# Sheet4.net
KiCad netlist of a schematic drawn in Altium Designer
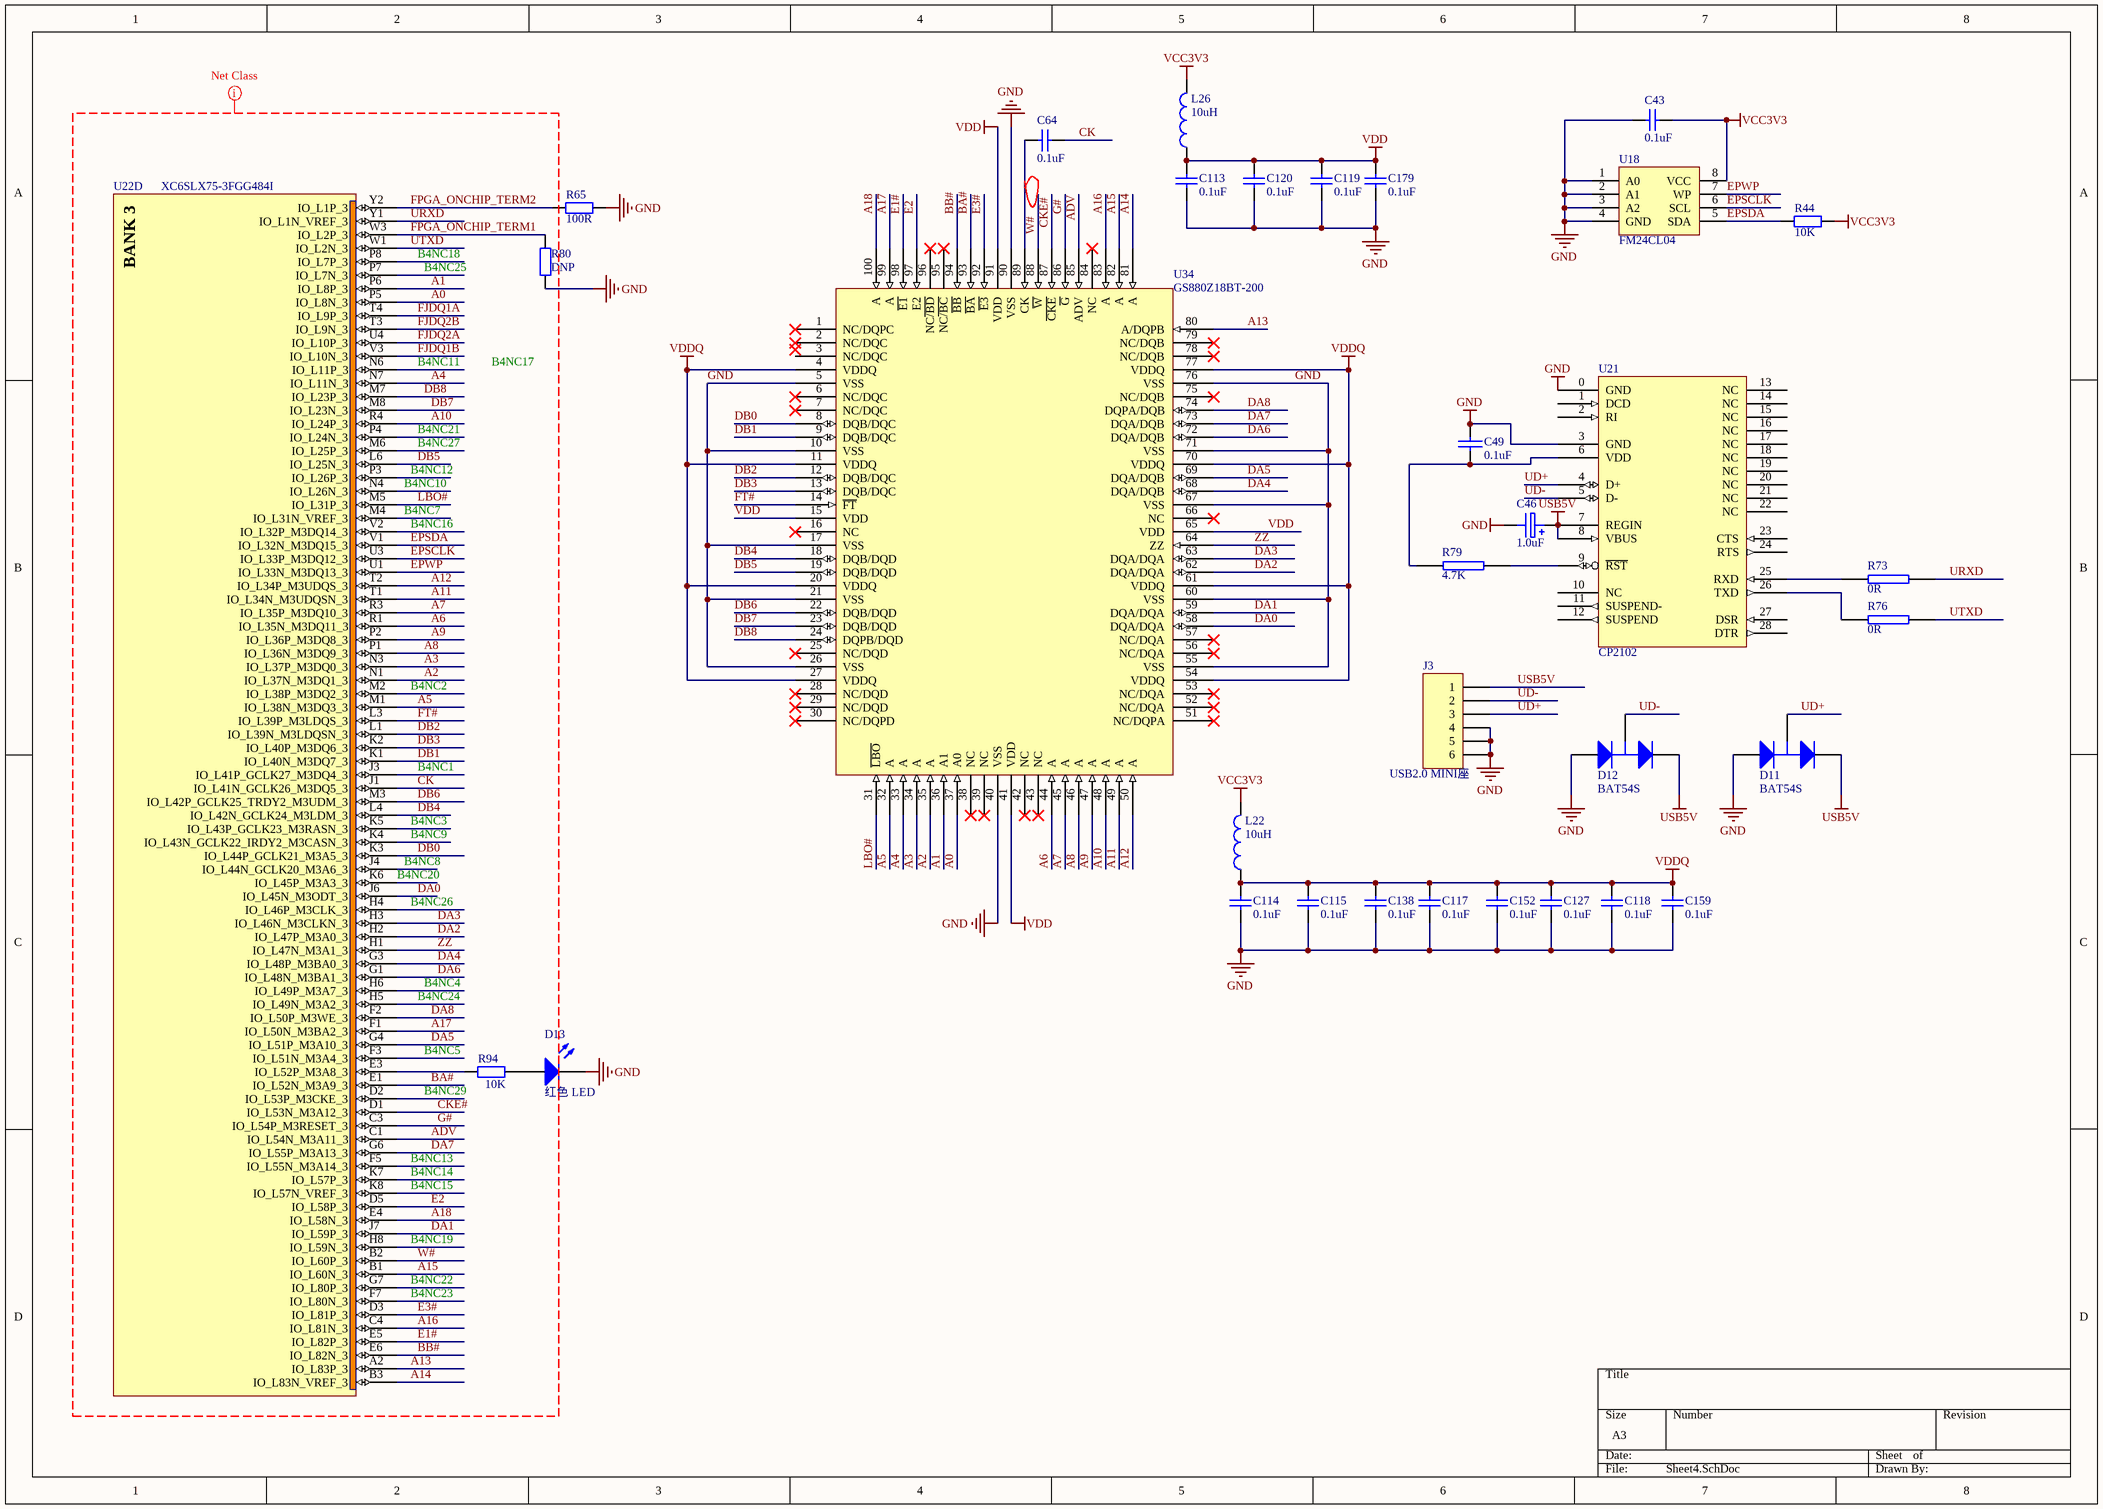
[diagram p0: Sheet4.SchDoc]

(export (version "E")
  (design (tool "Eeschema 10.0.6"))
  (components
    (comp (ref "C43")
      (value "0.1uF")
      (footprint "0603C")
      (description "Capacitor")
      (fields (field (name "PUBLISHER") "Altium Limited"))
      (libsource (lib "Miscellaneous Devices") (part "Cap"))
    )
    (comp (ref "C46") (value "1.0uF") (footprint "0805C") (libsource (lib "*") (part "ELECTRO1")))
    (comp (ref "C49")
      (value "0.1uF")
      (footprint "0603C")
      (description "Capacitor")
      (libsource (lib "*") (part "CAP"))
    )
    (comp (ref "C64")
      (value "0.1uF")
      (footprint "0402C")
      (description "Capacitor")
      (fields (field (name "PUBLISHER") "Altium Limited"))
      (libsource (lib "Miscellaneous Devices") (part "Cap"))
    )
    (comp (ref "C113")
      (value "0.1uF")
      (footprint "0402C")
      (description "Capacitor")
      (fields (field (name "PUBLISHER") "Altium Limited"))
      (libsource (lib "Miscellaneous Devices") (part "Cap"))
    )
    (comp (ref "C114")
      (value "0.1uF")
      (footprint "0402C")
      (description "Capacitor")
      (fields (field (name "PUBLISHER") "Altium Limited"))
      (libsource (lib "Miscellaneous Devices") (part "Cap"))
    )
    (comp (ref "C115")
      (value "0.1uF")
      (footprint "0402C")
      (description "Capacitor")
      (fields (field (name "PUBLISHER") "Altium Limited"))
      (libsource (lib "Miscellaneous Devices") (part "Cap"))
    )
    (comp (ref "C117")
      (value "0.1uF")
      (footprint "0402C")
      (description "Capacitor")
      (fields (field (name "PUBLISHER") "Altium Limited"))
      (libsource (lib "Miscellaneous Devices") (part "Cap"))
    )
    (comp (ref "C118")
      (value "0.1uF")
      (footprint "0402C")
      (description "Capacitor")
      (fields (field (name "PUBLISHER") "Altium Limited"))
      (libsource (lib "Miscellaneous Devices") (part "Cap"))
    )
    (comp (ref "C119")
      (value "0.1uF")
      (footprint "0402C")
      (description "Capacitor")
      (fields (field (name "PUBLISHER") "Altium Limited"))
      (libsource (lib "Miscellaneous Devices") (part "Cap"))
    )
    (comp (ref "C120")
      (value "0.1uF")
      (footprint "0402C")
      (description "Capacitor")
      (fields (field (name "PUBLISHER") "Altium Limited"))
      (libsource (lib "Miscellaneous Devices") (part "Cap"))
    )
    (comp (ref "C127")
      (value "0.1uF")
      (footprint "0402C")
      (description "Capacitor")
      (fields (field (name "PUBLISHER") "Altium Limited"))
      (libsource (lib "Miscellaneous Devices") (part "Cap"))
    )
    (comp (ref "C138")
      (value "0.1uF")
      (footprint "0402C")
      (description "Capacitor")
      (fields (field (name "PUBLISHER") "Altium Limited"))
      (libsource (lib "Miscellaneous Devices") (part "Cap"))
    )
    (comp (ref "C152")
      (value "0.1uF")
      (footprint "0402C")
      (description "Capacitor")
      (fields (field (name "PUBLISHER") "Altium Limited"))
      (libsource (lib "Miscellaneous Devices") (part "Cap"))
    )
    (comp (ref "C159")
      (value "0.1uF")
      (footprint "0402C")
      (description "Capacitor")
      (fields (field (name "PUBLISHER") "Altium Limited"))
      (libsource (lib "Miscellaneous Devices") (part "Cap"))
    )
    (comp (ref "C179")
      (value "0.1uF")
      (footprint "0402C")
      (description "Capacitor")
      (fields (field (name "PUBLISHER") "Altium Limited"))
      (libsource (lib "Miscellaneous Devices") (part "Cap"))
    )
    (comp (ref "D11")
      (value "BAT54S")
      (footprint "SOT23-3L")
      (description "Silicon Switching Diode Array for High-Speed Switching")
      (fields (field (name "PUBLISHER") "Altium Limited"))
      (libsource (lib "Infineon Discrete Diode") (part "BAV99"))
    )
    (comp (ref "D12")
      (value "BAT54S")
      (footprint "SOT23-3L")
      (description "Silicon Switching Diode Array for High-Speed Switching")
      (fields (field (name "PUBLISHER") "Altium Limited"))
      (libsource (lib "Infineon Discrete Diode") (part "BAV99"))
    )
    (comp (ref "D13")
      (value "红色 LED")
      (footprint "0805LED")
      (description "Typical INFRARED GaAs LED")
      (fields (field (name "PUBLISHER") "Altium Limited"))
      (libsource (lib "Miscellaneous Devices") (part "LED0"))
    )
    (comp (ref "J3")
      (value "USB2.0 MINI座")
      (footprint "HDR1X4")
      (description "Header, 6-Pin")
      (fields (field (name "PUBLISHER") "Altium Limited"))
      (libsource (lib "Miscellaneous Connectors") (part "Header 6"))
    )
    (comp (ref "L22")
      (value "10uH")
      (footprint "1206L")
      (description "Inductor")
      (fields (field (name "PUBLISHER") "Altium Limited"))
      (libsource (lib "Miscellaneous Devices") (part "Inductor"))
    )
    (comp (ref "L26")
      (value "10uH")
      (footprint "1206L")
      (description "Inductor")
      (fields (field (name "PUBLISHER") "Altium Limited"))
      (libsource (lib "Miscellaneous Devices") (part "Inductor"))
    )
    (comp (ref "R44") (value "10K") (footprint "0603R") (libsource (lib "Custom Schlib") (part "Resistor")))
    (comp (ref "R65")
      (value "100R")
      (footprint "0603R")
      (description "Resistor")
      (fields (field (name "PUBLISHER") "Altium Limited"))
      (libsource (lib "Miscellaneous Devices") (part "Res2"))
    )
    (comp (ref "R73") (value "0R") (footprint "0603R") (libsource (lib "*") (part "RES2")))
    (comp (ref "R76") (value "0R") (footprint "0603R") (libsource (lib "*") (part "RES2")))
    (comp (ref "R79") (value "4.7K") (footprint "0603R") (libsource (lib "*") (part "RES2")))
    (comp (ref "R80")
      (value "DNP")
      (footprint "0603R")
      (description "Resistor")
      (fields (field (name "PUBLISHER") "Altium Limited"))
      (libsource (lib "") (part "Res2_1"))
    )
    (comp (ref "R94")
      (value "10K")
      (footprint "0603R")
      (description "Resistor")
      (fields (field (name "PUBLISHER") "Altium Limited"))
      (libsource (lib "Miscellaneous Devices") (part "Res2"))
    )
    (comp (ref "U18")
      (value "FM24CL04")
      (footprint "so_8")
      (libsource (lib "Custom Schlib") (part "FM24CL04"))
    )
    (comp (ref "U21")
      (value "CP2102")
      (footprint "MLP-28")
      (description "433MHZ PSK/FM/AM/Data Transceiver")
      (libsource (lib "*") (part "RF2906(28)"))
    )
    (comp (ref "U22")
      (value "XC6SLX75-3FGG484I")
      (footprint "FGG484")
      (fields (field (name "PUBLISHER") "Altium Limited"))
      (libsource (lib "Xilinx Spartan-6") (part "XC6SLX45-L1FGG484I"))
    )
    (comp (ref "U34")
      (value "GS880Z18BT-200")
      (footprint "QFP65P1680X2280-100N")
      (libsource (lib "Mpd_Fpga_2") (part "GS880Z18BT100"))
    )
  )
  (nets
    (net (code "1") (name "/A0") (class "Default")
      (node (ref "U22") (pin "P5") (pinfunction "IO_L8N_3_P5") (pintype "bidirectional"))
      (node (ref "U34") (pin "37") (pinfunction "A0_37") (pintype "input"))
    )
    (net (code "2") (name "/A1") (class "Default")
      (node (ref "U22") (pin "P6") (pinfunction "IO_L8P_3_P6") (pintype "bidirectional"))
      (node (ref "U34") (pin "36") (pinfunction "A1_36") (pintype "input"))
    )
    (net (code "3") (name "/A2") (class "Default")
      (node (ref "U22") (pin "N1") (pinfunction "IO_L37N_M3DQ1_3_N1") (pintype "bidirectional"))
      (node (ref "U34") (pin "35") (pinfunction "A_35") (pintype "input"))
    )
    (net (code "4") (name "/A3") (class "Default")
      (node (ref "U22") (pin "N3") (pinfunction "IO_L37P_M3DQ0_3_N3") (pintype "bidirectional"))
      (node (ref "U34") (pin "34") (pinfunction "A_34") (pintype "input"))
    )
    (net (code "5") (name "/A4") (class "Default")
      (node (ref "U22") (pin "N7") (pinfunction "IO_L11N_3_N7") (pintype "bidirectional"))
      (node (ref "U34") (pin "33") (pinfunction "A_33") (pintype "input"))
    )
    (net (code "6") (name "/A5") (class "Default")
      (node (ref "U22") (pin "M1") (pinfunction "IO_L38N_M3DQ3_3_M1") (pintype "bidirectional"))
      (node (ref "U34") (pin "32") (pinfunction "A_32") (pintype "input"))
    )
    (net (code "7") (name "/A6") (class "Default")
      (node (ref "U22") (pin "R1") (pinfunction "IO_L35N_M3DQ11_3_R1") (pintype "bidirectional"))
      (node (ref "U34") (pin "44") (pinfunction "A_44") (pintype "input"))
    )
    (net (code "8") (name "/A7") (class "Default")
      (node (ref "U22") (pin "R3") (pinfunction "IO_L35P_M3DQ10_3_R3") (pintype "bidirectional"))
      (node (ref "U34") (pin "45") (pinfunction "A_45") (pintype "input"))
    )
    (net (code "9") (name "/A8") (class "Default")
      (node (ref "U22") (pin "P1") (pinfunction "IO_L36N_M3DQ9_3_P1") (pintype "bidirectional"))
      (node (ref "U34") (pin "46") (pinfunction "A_46") (pintype "input"))
    )
    (net (code "10") (name "/A9") (class "Default")
      (node (ref "U22") (pin "P2") (pinfunction "IO_L36P_M3DQ8_3_P2") (pintype "bidirectional"))
      (node (ref "U34") (pin "47") (pinfunction "A_47") (pintype "input"))
    )
    (net (code "11") (name "/A10") (class "Default")
      (node (ref "U22") (pin "R4") (pinfunction "IO_L24P_3_R4") (pintype "bidirectional"))
      (node (ref "U34") (pin "48") (pinfunction "A_48") (pintype "input"))
    )
    (net (code "12") (name "/A11") (class "Default")
      (node (ref "U22") (pin "T1") (pinfunction "IO_L34N_M3UDQSN_3_T1") (pintype "bidirectional"))
      (node (ref "U34") (pin "49") (pinfunction "A_49") (pintype "input"))
    )
    (net (code "13") (name "/A12") (class "Default")
      (node (ref "U22") (pin "T2") (pinfunction "IO_L34P_M3UDQS_3_T2") (pintype "bidirectional"))
      (node (ref "U34") (pin "50") (pinfunction "A_50") (pintype "input"))
    )
    (net (code "14") (name "/A13") (class "Default")
      (node (ref "U22") (pin "A2") (pinfunction "IO_L83P_3_A2") (pintype "bidirectional"))
      (node (ref "U34") (pin "80") (pinfunction "A/DQPB_80") (pintype "input"))
    )
    (net (code "15") (name "/A14") (class "Default")
      (node (ref "U22") (pin "B3") (pinfunction "IO_L83N_VREF_3_B3") (pintype "bidirectional"))
      (node (ref "U34") (pin "81") (pinfunction "A_81") (pintype "input"))
    )
    (net (code "16") (name "/A15") (class "Default")
      (node (ref "U22") (pin "B1") (pinfunction "IO_L60N_3_B1") (pintype "bidirectional"))
      (node (ref "U34") (pin "82") (pinfunction "A_82") (pintype "input"))
    )
    (net (code "17") (name "/A16") (class "Default")
      (node (ref "U22") (pin "C4") (pinfunction "IO_L81N_3_C4") (pintype "bidirectional"))
      (node (ref "U34") (pin "83") (pinfunction "A_83") (pintype "input"))
    )
    (net (code "18") (name "/A17") (class "Default")
      (node (ref "U22") (pin "F1") (pinfunction "IO_L50N_M3BA2_3_F1") (pintype "bidirectional"))
      (node (ref "U34") (pin "99") (pinfunction "A_99") (pintype "input"))
    )
    (net (code "19") (name "/A18") (class "Default")
      (node (ref "U22") (pin "E4") (pinfunction "IO_L58N_3_E4") (pintype "bidirectional"))
      (node (ref "U34") (pin "100") (pinfunction "A_100") (pintype "input"))
    )
    (net (code "20") (name "/ADV") (class "Default")
      (node (ref "U22") (pin "C1") (pinfunction "IO_L54N_M3A11_3_C1") (pintype "bidirectional"))
      (node (ref "U34") (pin "85") (pinfunction "ADV_85") (pintype "input"))
    )
    (net (code "21") (name "/B4NC1") (class "Default")
      (node (ref "U22") (pin "J3") (pinfunction "IO_L41P_GCLK27_M3DQ4_3_J3") (pintype "bidirectional"))
    )
    (net (code "22") (name "/B4NC2") (class "Default")
      (node (ref "U22") (pin "M2") (pinfunction "IO_L38P_M3DQ2_3_M2") (pintype "bidirectional"))
    )
    (net (code "23") (name "/B4NC3") (class "Default")
      (node (ref "U22") (pin "K5") (pinfunction "IO_L43P_GCLK23_M3RASN_3_K5") (pintype "bidirectional"))
    )
    (net (code "24") (name "/B4NC4") (class "Default")
      (node (ref "U22") (pin "H6") (pinfunction "IO_L49P_M3A7_3_H6") (pintype "bidirectional"))
    )
    (net (code "25") (name "/B4NC5") (class "Default")
      (node (ref "U22") (pin "F3") (pinfunction "IO_L51N_M3A4_3_F3") (pintype "bidirectional"))
    )
    (net (code "26") (name "/B4NC7") (class "Default")
      (node (ref "U22") (pin "M4") (pinfunction "IO_L31N_VREF_3_M4") (pintype "bidirectional"))
    )
    (net (code "27") (name "/B4NC8") (class "Default")
      (node (ref "U22") (pin "J4") (pinfunction "IO_L44N_GCLK20_M3A6_3_J4") (pintype "bidirectional"))
    )
    (net (code "28") (name "/B4NC9") (class "Default")
      (node (ref "U22") (pin "K4") (pinfunction "IO_L43N_GCLK22_IRDY2_M3CASN_3_K4") (pintype "bidirectional"))
    )
    (net (code "29") (name "/B4NC10") (class "Default")
      (node (ref "U22") (pin "N4") (pinfunction "IO_L26N_3_N4") (pintype "bidirectional"))
    )
    (net (code "30") (name "/B4NC11") (class "Default")
      (node (ref "U22") (pin "N6") (pinfunction "IO_L11P_3_N6") (pintype "bidirectional"))
    )
    (net (code "31") (name "/B4NC12") (class "Default")
      (node (ref "U22") (pin "P3") (pinfunction "IO_L26P_3_P3") (pintype "bidirectional"))
    )
    (net (code "32") (name "/B4NC13") (class "Default")
      (node (ref "U22") (pin "F5") (pinfunction "IO_L55N_M3A14_3_F5") (pintype "bidirectional"))
    )
    (net (code "33") (name "/B4NC14") (class "Default")
      (node (ref "U22") (pin "K7") (pinfunction "IO_L57P_3_K7") (pintype "bidirectional"))
    )
    (net (code "34") (name "/B4NC15") (class "Default")
      (node (ref "U22") (pin "K8") (pinfunction "IO_L57N_VREF_3_K8") (pintype "bidirectional"))
    )
    (net (code "35") (name "/B4NC16") (class "Default")
      (node (ref "U22") (pin "V2") (pinfunction "IO_L32P_M3DQ14_3_V2") (pintype "bidirectional"))
    )
    (net (code "37") (name "/B4NC18") (class "Default")
      (node (ref "U22") (pin "P8") (pinfunction "IO_L7P_3_P8") (pintype "bidirectional"))
    )
    (net (code "38") (name "/B4NC19") (class "Default")
      (node (ref "U22") (pin "H8") (pinfunction "IO_L59N_3_H8") (pintype "bidirectional"))
    )
    (net (code "39") (name "/B4NC20") (class "Default")
      (node (ref "U22") (pin "K6") (pinfunction "IO_L45P_M3A3_3_K6") (pintype "bidirectional"))
    )
    (net (code "40") (name "/B4NC21") (class "Default")
      (node (ref "U22") (pin "P4") (pinfunction "IO_L24N_3_P4") (pintype "bidirectional"))
    )
    (net (code "41") (name "/B4NC22") (class "Default")
      (node (ref "U22") (pin "G7") (pinfunction "IO_L80P_3_G7") (pintype "bidirectional"))
    )
    (net (code "42") (name "/B4NC23") (class "Default")
      (node (ref "U22") (pin "F7") (pinfunction "IO_L80N_3_F7") (pintype "bidirectional"))
    )
    (net (code "43") (name "/B4NC24") (class "Default")
      (node (ref "U22") (pin "H5") (pinfunction "IO_L49N_M3A2_3_H5") (pintype "bidirectional"))
    )
    (net (code "44") (name "/B4NC25") (class "Default")
      (node (ref "U22") (pin "P7") (pinfunction "IO_L7N_3_P7") (pintype "bidirectional"))
    )
    (net (code "45") (name "/B4NC26") (class "Default")
      (node (ref "U22") (pin "H4") (pinfunction "IO_L46P_M3CLK_3_H4") (pintype "bidirectional"))
    )
    (net (code "46") (name "/B4NC27") (class "Default")
      (node (ref "U22") (pin "M6") (pinfunction "IO_L25P_3_M6") (pintype "bidirectional"))
    )
    (net (code "47") (name "/B4NC29") (class "Default")
      (node (ref "U22") (pin "D2") (pinfunction "IO_L53P_M3CKE_3_D2") (pintype "bidirectional"))
    )
    (net (code "48") (name "/BA#") (class "Default")
      (node (ref "U22") (pin "E1") (pinfunction "IO_L52N_M3A9_3_E1") (pintype "bidirectional"))
      (node (ref "U34") (pin "93") (pinfunction "~{BA}_93") (pintype "input"))
    )
    (net (code "49") (name "/BB#") (class "Default")
      (node (ref "U22") (pin "E6") (pinfunction "IO_L82N_3_E6") (pintype "bidirectional"))
      (node (ref "U34") (pin "94") (pinfunction "~{BB}_94") (pintype "input"))
    )
    (net (code "50") (name "/CK") (class "Default")
      (node (ref "C64") (pin "1") (pinfunction "1_1") (pintype "passive"))
      (node (ref "U22") (pin "J1") (pinfunction "IO_L41N_GCLK26_M3DQ5_3_J1") (pintype "bidirectional"))
    )
    (net (code "51") (name "/CKE#") (class "Default")
      (node (ref "U22") (pin "D1") (pinfunction "IO_L53N_M3A12_3_D1") (pintype "bidirectional"))
      (node (ref "U34") (pin "87") (pinfunction "~{CKE}_87") (pintype "input"))
    )
    (net (code "52") (name "/DA0") (class "Default")
      (node (ref "U22") (pin "J6") (pinfunction "IO_L45N_M3ODT_3_J6") (pintype "bidirectional"))
      (node (ref "U34") (pin "58") (pinfunction "DQA/DQA_58") (pintype "bidirectional"))
    )
    (net (code "53") (name "/DA1") (class "Default")
      (node (ref "U22") (pin "J7") (pinfunction "IO_L59P_3_J7") (pintype "bidirectional"))
      (node (ref "U34") (pin "59") (pinfunction "DQA/DQA_59") (pintype "bidirectional"))
    )
    (net (code "54") (name "/DA2") (class "Default")
      (node (ref "U22") (pin "H2") (pinfunction "IO_L47P_M3A0_3_H2") (pintype "bidirectional"))
      (node (ref "U34") (pin "62") (pinfunction "DQA/DQA_62") (pintype "bidirectional"))
    )
    (net (code "55") (name "/DA3") (class "Default")
      (node (ref "U22") (pin "H3") (pinfunction "IO_L46N_M3CLKN_3_H3") (pintype "bidirectional"))
      (node (ref "U34") (pin "63") (pinfunction "DQA/DQA_63") (pintype "bidirectional"))
    )
    (net (code "56") (name "/DA4") (class "Default")
      (node (ref "U22") (pin "G3") (pinfunction "IO_L48P_M3BA0_3_G3") (pintype "bidirectional"))
      (node (ref "U34") (pin "68") (pinfunction "DQA/DQB_68") (pintype "bidirectional"))
    )
    (net (code "57") (name "/DA5") (class "Default")
      (node (ref "U22") (pin "G4") (pinfunction "IO_L51P_M3A10_3_G4") (pintype "bidirectional"))
      (node (ref "U34") (pin "69") (pinfunction "DQA/DQB_69") (pintype "bidirectional"))
    )
    (net (code "58") (name "/DA6") (class "Default")
      (node (ref "U22") (pin "G1") (pinfunction "IO_L48N_M3BA1_3_G1") (pintype "bidirectional"))
      (node (ref "U34") (pin "72") (pinfunction "DQA/DQB_72") (pintype "bidirectional"))
    )
    (net (code "59") (name "/DA7") (class "Default")
      (node (ref "U22") (pin "G6") (pinfunction "IO_L55P_M3A13_3_G6") (pintype "bidirectional"))
      (node (ref "U34") (pin "73") (pinfunction "DQA/DQB_73") (pintype "bidirectional"))
    )
    (net (code "60") (name "/DA8") (class "Default")
      (node (ref "U22") (pin "F2") (pinfunction "IO_L50P_M3WE_3_F2") (pintype "bidirectional"))
      (node (ref "U34") (pin "74") (pinfunction "DQPA/DQB_74") (pintype "bidirectional"))
    )
    (net (code "61") (name "/DB0") (class "Default")
      (node (ref "U22") (pin "K3") (pinfunction "IO_L44P_GCLK21_M3A5_3_K3") (pintype "bidirectional"))
      (node (ref "U34") (pin "8") (pinfunction "DQB/DQC_8") (pintype "bidirectional"))
    )
    (net (code "62") (name "/DB1") (class "Default")
      (node (ref "U22") (pin "K1") (pinfunction "IO_L40N_M3DQ7_3_K1") (pintype "bidirectional"))
      (node (ref "U34") (pin "9") (pinfunction "DQB/DQC_9") (pintype "bidirectional"))
    )
    (net (code "63") (name "/DB2") (class "Default")
      (node (ref "U22") (pin "L1") (pinfunction "IO_L39N_M3LDQSN_3_L1") (pintype "bidirectional"))
      (node (ref "U34") (pin "12") (pinfunction "DQB/DQC_12") (pintype "bidirectional"))
    )
    (net (code "64") (name "/DB3") (class "Default")
      (node (ref "U22") (pin "K2") (pinfunction "IO_L40P_M3DQ6_3_K2") (pintype "bidirectional"))
      (node (ref "U34") (pin "13") (pinfunction "DQB/DQC_13") (pintype "bidirectional"))
    )
    (net (code "65") (name "/DB4") (class "Default")
      (node (ref "U22") (pin "L4") (pinfunction "IO_L42N_GCLK24_M3LDM_3_L4") (pintype "bidirectional"))
      (node (ref "U34") (pin "18") (pinfunction "DQB/DQD_18") (pintype "bidirectional"))
    )
    (net (code "66") (name "/DB5") (class "Default")
      (node (ref "U22") (pin "L6") (pinfunction "IO_L25N_3_L6") (pintype "bidirectional"))
      (node (ref "U34") (pin "19") (pinfunction "DQB/DQD_19") (pintype "bidirectional"))
    )
    (net (code "67") (name "/DB6") (class "Default")
      (node (ref "U22") (pin "M3") (pinfunction "IO_L42P_GCLK25_TRDY2_M3UDM_3_M3") (pintype "bidirectional"))
      (node (ref "U34") (pin "22") (pinfunction "DQB/DQD_22") (pintype "bidirectional"))
    )
    (net (code "68") (name "/DB7") (class "Default")
      (node (ref "U22") (pin "M8") (pinfunction "IO_L23N_3_M8") (pintype "bidirectional"))
      (node (ref "U34") (pin "23") (pinfunction "DQB/DQD_23") (pintype "bidirectional"))
    )
    (net (code "69") (name "/DB8") (class "Default")
      (node (ref "U22") (pin "M7") (pinfunction "IO_L23P_3_M7") (pintype "bidirectional"))
      (node (ref "U34") (pin "24") (pinfunction "DQPB/DQD_24") (pintype "bidirectional"))
    )
    (net (code "70") (name "/E1#") (class "Default")
      (node (ref "U22") (pin "E5") (pinfunction "IO_L82P_3_E5") (pintype "bidirectional"))
      (node (ref "U34") (pin "98") (pinfunction "~{E1}_98") (pintype "input"))
    )
    (net (code "71") (name "/E2") (class "Default")
      (node (ref "U22") (pin "D5") (pinfunction "IO_L58P_3_D5") (pintype "bidirectional"))
      (node (ref "U34") (pin "97") (pinfunction "E2_97") (pintype "input"))
    )
    (net (code "72") (name "/E3#") (class "Default")
      (node (ref "U22") (pin "D3") (pinfunction "IO_L81P_3_D3") (pintype "bidirectional"))
      (node (ref "U34") (pin "92") (pinfunction "~{E3}_92") (pintype "input"))
    )
    (net (code "73") (name "/EPSCLK") (class "Default")
      (node (ref "U18") (pin "6") (pinfunction "SCL_6") (pintype "passive"))
      (node (ref "U22") (pin "U3") (pinfunction "IO_L33P_M3DQ12_3_U3") (pintype "bidirectional"))
    )
    (net (code "74") (name "/EPSDA") (class "Default")
      (node (ref "R44") (pin "1") (pinfunction "1_1") (pintype "passive"))
      (node (ref "U18") (pin "5") (pinfunction "SDA_5") (pintype "passive"))
      (node (ref "U22") (pin "V1") (pinfunction "IO_L32N_M3DQ15_3_V1") (pintype "bidirectional"))
    )
    (net (code "75") (name "/EPWP") (class "Default")
      (node (ref "U18") (pin "7") (pinfunction "WP_7") (pintype "passive"))
      (node (ref "U22") (pin "U1") (pinfunction "IO_L33N_M3DQ13_3_U1") (pintype "bidirectional"))
    )
    (net (code "76") (name "/FJDQ1A") (class "Default")
      (node (ref "U22") (pin "T4") (pinfunction "IO_L9P_3_T4") (pintype "bidirectional"))
    )
    (net (code "77") (name "/FJDQ1B") (class "Default")
      (node (ref "U22") (pin "V3") (pinfunction "IO_L10N_3_V3") (pintype "bidirectional"))
    )
    (net (code "78") (name "/FJDQ2A") (class "Default")
      (node (ref "U22") (pin "U4") (pinfunction "IO_L10P_3_U4") (pintype "bidirectional"))
    )
    (net (code "79") (name "/FJDQ2B") (class "Default")
      (node (ref "U22") (pin "T3") (pinfunction "IO_L9N_3_T3") (pintype "bidirectional"))
    )
    (net (code "80") (name "/FPGA_ONCHIP_TERM1") (class "Default")
      (node (ref "R80") (pin "1") (pinfunction "1_1") (pintype "passive"))
      (node (ref "U22") (pin "W3") (pinfunction "IO_L2P_3_W3") (pintype "bidirectional"))
    )
    (net (code "81") (name "/FPGA_ONCHIP_TERM2") (class "Default")
      (node (ref "R65") (pin "1") (pinfunction "1_1") (pintype "passive"))
      (node (ref "U22") (pin "Y2") (pinfunction "IO_L1P_3_Y2") (pintype "bidirectional"))
    )
    (net (code "82") (name "/FT#") (class "Default")
      (node (ref "U22") (pin "L3") (pinfunction "IO_L39P_M3LDQS_3_L3") (pintype "bidirectional"))
      (node (ref "U34") (pin "14") (pinfunction "~{FT}_14") (pintype "input"))
    )
    (net (code "83") (name "/G#") (class "Default")
      (node (ref "U22") (pin "C3") (pinfunction "IO_L54P_M3RESET_3_C3") (pintype "bidirectional"))
      (node (ref "U34") (pin "86") (pinfunction "~{G}_86") (pintype "input"))
    )
    (net (code "84") (name "/LBO#") (class "Default")
      (node (ref "U22") (pin "M5") (pinfunction "IO_L31P_3_M5") (pintype "bidirectional"))
      (node (ref "U34") (pin "31") (pinfunction "~{LBO}_31") (pintype "input"))
    )
    (net (code "85") (name "/UD+") (class "Default")
      (node (ref "D11") (pin "3") (pinfunction "C_3") (pintype "passive"))
      (node (ref "J3") (pin "3") (pinfunction "3_3") (pintype "passive"))
      (node (ref "U21") (pin "4") (pinfunction "D+_4") (pintype "bidirectional"))
    )
    (net (code "86") (name "/UD-") (class "Default")
      (node (ref "D12") (pin "3") (pinfunction "C_3") (pintype "passive"))
      (node (ref "J3") (pin "2") (pinfunction "2_2") (pintype "passive"))
      (node (ref "U21") (pin "5") (pinfunction "D-_5") (pintype "bidirectional"))
    )
    (net (code "87") (name "/URXD") (class "Default")
      (node (ref "R73") (pin "1") (pinfunction "1_1") (pintype "passive"))
      (node (ref "U22") (pin "Y1") (pinfunction "IO_L1N_VREF_3_Y1") (pintype "bidirectional"))
    )
    (net (code "88") (name "/UTXD") (class "Default")
      (node (ref "R76") (pin "1") (pinfunction "1_1") (pintype "passive"))
      (node (ref "U22") (pin "W1") (pinfunction "IO_L2N_3_W1") (pintype "bidirectional"))
    )
    (net (code "89") (name "/W#") (class "Default")
      (node (ref "U22") (pin "B2") (pinfunction "IO_L60P_3_B2") (pintype "bidirectional"))
      (node (ref "U34") (pin "88") (pinfunction "~{W}_88") (pintype "input"))
    )
    (net (code "90") (name "/ZZ") (class "Default")
      (node (ref "U22") (pin "H1") (pinfunction "IO_L47N_M3A1_3_H1") (pintype "bidirectional"))
      (node (ref "U34") (pin "64") (pinfunction "ZZ_64") (pintype "input"))
    )
    (net (code "91") (name "GND") (class "Default")
      (node (ref "C113") (pin "1") (pinfunction "1_1") (pintype "passive"))
      (node (ref "C114") (pin "1") (pinfunction "1_1") (pintype "passive"))
      (node (ref "C115") (pin "1") (pinfunction "1_1") (pintype "passive"))
      (node (ref "C117") (pin "1") (pinfunction "1_1") (pintype "passive"))
      (node (ref "C118") (pin "1") (pinfunction "1_1") (pintype "passive"))
      (node (ref "C119") (pin "1") (pinfunction "1_1") (pintype "passive"))
      (node (ref "C120") (pin "1") (pinfunction "1_1") (pintype "passive"))
      (node (ref "C127") (pin "1") (pinfunction "1_1") (pintype "passive"))
      (node (ref "C138") (pin "1") (pinfunction "1_1") (pintype "passive"))
      (node (ref "C152") (pin "1") (pinfunction "1_1") (pintype "passive"))
      (node (ref "C159") (pin "1") (pinfunction "1_1") (pintype "passive"))
      (node (ref "C179") (pin "1") (pinfunction "1_1") (pintype "passive"))
      (node (ref "C43") (pin "2") (pinfunction "2_2") (pintype "passive"))
      (node (ref "C46") (pin "2") (pintype "passive"))
      (node (ref "C49") (pin "2") (pinfunction "2_2") (pintype "passive"))
      (node (ref "D11") (pin "1") (pinfunction "A_1") (pintype "passive"))
      (node (ref "D12") (pin "1") (pinfunction "A_1") (pintype "passive"))
      (node (ref "D13") (pin "2") (pinfunction "K_2") (pintype "passive"))
      (node (ref "J3") (pin "4") (pinfunction "4_4") (pintype "passive"))
      (node (ref "J3") (pin "5") (pinfunction "5_5") (pintype "passive"))
      (node (ref "J3") (pin "6") (pinfunction "6_6") (pintype "passive"))
      (node (ref "R65") (pin "2") (pinfunction "2_2") (pintype "passive"))
      (node (ref "R80") (pin "2") (pinfunction "2_2") (pintype "passive"))
      (node (ref "U18") (pin "1") (pinfunction "A0_1") (pintype "passive"))
      (node (ref "U18") (pin "2") (pinfunction "A1_2") (pintype "passive"))
      (node (ref "U18") (pin "3") (pinfunction "A2_3") (pintype "passive"))
      (node (ref "U18") (pin "4") (pinfunction "GND_4") (pintype "passive"))
      (node (ref "U21") (pin "0") (pinfunction "GND_0") (pintype "power_in"))
      (node (ref "U21") (pin "3") (pinfunction "GND_3") (pintype "power_in"))
      (node (ref "U34") (pin "10") (pinfunction "VSS_10") (pintype "power_in"))
      (node (ref "U34") (pin "17") (pinfunction "VSS_17") (pintype "power_in"))
      (node (ref "U34") (pin "21") (pinfunction "VSS_21") (pintype "power_in"))
      (node (ref "U34") (pin "26") (pinfunction "VSS_26") (pintype "power_in"))
      (node (ref "U34") (pin "40") (pinfunction "VSS_40") (pintype "power_in"))
      (node (ref "U34") (pin "5") (pinfunction "VSS_5") (pintype "power_in"))
      (node (ref "U34") (pin "55") (pinfunction "VSS_55") (pintype "power_in"))
      (node (ref "U34") (pin "60") (pinfunction "VSS_60") (pintype "power_in"))
      (node (ref "U34") (pin "67") (pinfunction "VSS_67") (pintype "power_in"))
      (node (ref "U34") (pin "71") (pinfunction "VSS_71") (pintype "power_in"))
      (node (ref "U34") (pin "76") (pinfunction "VSS_76") (pintype "power_in"))
      (node (ref "U34") (pin "90") (pinfunction "VSS_90") (pintype "power_in"))
    )
    (net (code "92") (name "Net-(D13-A)") (class "Default")
      (node (ref "D13") (pin "1") (pinfunction "A_1") (pintype "passive"))
      (node (ref "R94") (pin "2") (pinfunction "2_2") (pintype "passive"))
    )
    (net (code "93") (name "Net-(U21-RXD)") (class "Default")
      (node (ref "R73") (pin "2") (pinfunction "2_2") (pintype "passive"))
      (node (ref "U21") (pin "25") (pinfunction "RXD_25") (pintype "input"))
    )
    (net (code "94") (name "Net-(U21-TXD)") (class "Default")
      (node (ref "R76") (pin "2") (pinfunction "2_2") (pintype "passive"))
      (node (ref "U21") (pin "26") (pinfunction "TXD_26") (pintype "output"))
    )
    (net (code "95") (name "Net-(U21-VDD)") (class "Default")
      (node (ref "C49") (pin "1") (pinfunction "1_1") (pintype "passive"))
      (node (ref "R79") (pin "2") (pinfunction "2_2") (pintype "passive"))
      (node (ref "U21") (pin "6") (pinfunction "VDD_6") (pintype "power_in"))
    )
    (net (code "96") (name "Net-(U21-~{RST})") (class "Default")
      (node (ref "R79") (pin "1") (pinfunction "1_1") (pintype "passive"))
      (node (ref "U21") (pin "9") (pinfunction "~{RST}_9") (pintype "bidirectional"))
    )
    (net (code "97") (name "Net-(U22D-IO_L52P_M3A8_3)") (class "Default")
      (node (ref "R94") (pin "1") (pinfunction "1_1") (pintype "passive"))
      (node (ref "U22") (pin "E3") (pinfunction "IO_L52P_M3A8_3_E3") (pintype "bidirectional"))
    )
    (net (code "98") (name "Net-(U34-CK)") (class "Default")
      (node (ref "C64") (pin "2") (pinfunction "2_2") (pintype "passive"))
      (node (ref "U34") (pin "89") (pinfunction "CK_89") (pintype "input"))
    )
    (net (code "99") (name "USB5V") (class "Default")
      (node (ref "C46") (pin "1") (pintype "passive"))
      (node (ref "D11") (pin "2") (pinfunction "K_2") (pintype "passive"))
      (node (ref "D12") (pin "2") (pinfunction "K_2") (pintype "passive"))
      (node (ref "J3") (pin "1") (pinfunction "1_1") (pintype "passive"))
      (node (ref "U21") (pin "7") (pinfunction "REGIN_7") (pintype "power_in"))
      (node (ref "U21") (pin "8") (pinfunction "VBUS_8") (pintype "input"))
    )
    (net (code "100") (name "VCC3V3") (class "Default")
      (node (ref "C43") (pin "1") (pinfunction "1_1") (pintype "passive"))
      (node (ref "L22") (pin "2") (pinfunction "2_2") (pintype "passive"))
      (node (ref "L26") (pin "2") (pinfunction "2_2") (pintype "passive"))
      (node (ref "R44") (pin "2") (pinfunction "2_2") (pintype "passive"))
      (node (ref "U18") (pin "8") (pinfunction "VCC_8") (pintype "passive"))
    )
    (net (code "101") (name "VDD") (class "Default")
      (node (ref "C113") (pin "2") (pinfunction "2_2") (pintype "passive"))
      (node (ref "C119") (pin "2") (pinfunction "2_2") (pintype "passive"))
      (node (ref "C120") (pin "2") (pinfunction "2_2") (pintype "passive"))
      (node (ref "C179") (pin "2") (pinfunction "2_2") (pintype "passive"))
      (node (ref "L26") (pin "1") (pinfunction "1_1") (pintype "passive"))
      (node (ref "U34") (pin "15") (pinfunction "VDD_15") (pintype "power_in"))
      (node (ref "U34") (pin "41") (pinfunction "VDD_41") (pintype "power_in"))
      (node (ref "U34") (pin "65") (pinfunction "VDD_65") (pintype "power_in"))
      (node (ref "U34") (pin "91") (pinfunction "VDD_91") (pintype "power_in"))
    )
    (net (code "102") (name "VDDQ") (class "Default")
      (node (ref "C114") (pin "2") (pinfunction "2_2") (pintype "passive"))
      (node (ref "C115") (pin "2") (pinfunction "2_2") (pintype "passive"))
      (node (ref "C117") (pin "2") (pinfunction "2_2") (pintype "passive"))
      (node (ref "C118") (pin "2") (pinfunction "2_2") (pintype "passive"))
      (node (ref "C127") (pin "2") (pinfunction "2_2") (pintype "passive"))
      (node (ref "C138") (pin "2") (pinfunction "2_2") (pintype "passive"))
      (node (ref "C152") (pin "2") (pinfunction "2_2") (pintype "passive"))
      (node (ref "C159") (pin "2") (pinfunction "2_2") (pintype "passive"))
      (node (ref "L22") (pin "1") (pinfunction "1_1") (pintype "passive"))
      (node (ref "U34") (pin "11") (pinfunction "VDDQ_11") (pintype "power_in"))
      (node (ref "U34") (pin "20") (pinfunction "VDDQ_20") (pintype "power_in"))
      (node (ref "U34") (pin "27") (pinfunction "VDDQ_27") (pintype "power_in"))
      (node (ref "U34") (pin "4") (pinfunction "VDDQ_4") (pintype "power_in"))
      (node (ref "U34") (pin "54") (pinfunction "VDDQ_54") (pintype "power_in"))
      (node (ref "U34") (pin "61") (pinfunction "VDDQ_61") (pintype "power_in"))
      (node (ref "U34") (pin "70") (pinfunction "VDDQ_70") (pintype "power_in"))
      (node (ref "U34") (pin "77") (pinfunction "VDDQ_77") (pintype "power_in"))
    )
    (net (code "103") (name "unconnected-(U21-CTS-Pad23)") (class "Default")
      (node (ref "U21") (pin "23") (pinfunction "CTS_23") (pintype "input"))
    )
    (net (code "104") (name "unconnected-(U21-DCD-Pad1)") (class "Default")
      (node (ref "U21") (pin "1") (pinfunction "DCD_1") (pintype "input"))
    )
    (net (code "105") (name "unconnected-(U21-DSR-Pad27)") (class "Default")
      (node (ref "U21") (pin "27") (pinfunction "DSR_27") (pintype "input"))
    )
    (net (code "106") (name "unconnected-(U21-DTR-Pad28)") (class "Default")
      (node (ref "U21") (pin "28") (pinfunction "DTR_28") (pintype "output"))
    )
    (net (code "107") (name "unconnected-(U21-NC-Pad10)") (class "Default")
      (node (ref "U21") (pin "10") (pinfunction "NC_10") (pintype "tri_state"))
    )
    (net (code "108") (name "unconnected-(U21-NC-Pad13)") (class "Default")
      (node (ref "U21") (pin "13") (pinfunction "NC_13") (pintype "tri_state"))
    )
    (net (code "109") (name "unconnected-(U21-NC-Pad14)") (class "Default")
      (node (ref "U21") (pin "14") (pinfunction "NC_14") (pintype "tri_state"))
    )
    (net (code "110") (name "unconnected-(U21-NC-Pad15)") (class "Default")
      (node (ref "U21") (pin "15") (pinfunction "NC_15") (pintype "tri_state"))
    )
    (net (code "111") (name "unconnected-(U21-NC-Pad16)") (class "Default")
      (node (ref "U21") (pin "16") (pinfunction "NC_16") (pintype "tri_state"))
    )
    (net (code "112") (name "unconnected-(U21-NC-Pad17)") (class "Default")
      (node (ref "U21") (pin "17") (pinfunction "NC_17") (pintype "tri_state"))
    )
    (net (code "113") (name "unconnected-(U21-NC-Pad18)") (class "Default")
      (node (ref "U21") (pin "18") (pinfunction "NC_18") (pintype "tri_state"))
    )
    (net (code "114") (name "unconnected-(U21-NC-Pad19)") (class "Default")
      (node (ref "U21") (pin "19") (pinfunction "NC_19") (pintype "tri_state"))
    )
    (net (code "115") (name "unconnected-(U21-NC-Pad20)") (class "Default")
      (node (ref "U21") (pin "20") (pinfunction "NC_20") (pintype "tri_state"))
    )
    (net (code "116") (name "unconnected-(U21-NC-Pad21)") (class "Default")
      (node (ref "U21") (pin "21") (pinfunction "NC_21") (pintype "tri_state"))
    )
    (net (code "117") (name "unconnected-(U21-NC-Pad22)") (class "Default")
      (node (ref "U21") (pin "22") (pinfunction "NC_22") (pintype "tri_state"))
    )
    (net (code "118") (name "unconnected-(U21-RI-Pad2)") (class "Default")
      (node (ref "U21") (pin "2") (pinfunction "RI_2") (pintype "input"))
    )
    (net (code "119") (name "unconnected-(U21-RTS-Pad24)") (class "Default")
      (node (ref "U21") (pin "24") (pinfunction "RTS_24") (pintype "output"))
    )
    (net (code "120") (name "unconnected-(U21-SUSPEND--Pad11)") (class "Default")
      (node (ref "U21") (pin "11") (pinfunction "SUSPEND-_11") (pintype "output"))
    )
    (net (code "121") (name "unconnected-(U21-SUSPEND-Pad12)") (class "Default")
      (node (ref "U21") (pin "12") (pinfunction "SUSPEND_12") (pintype "output"))
    )
    (net (code "122") (name "unconnected-(U34-NC-Pad16)") (class "Default")
      (node (ref "U34") (pin "16") (pinfunction "NC_16") (pintype "passive+no_connect"))
    )
    (net (code "123") (name "unconnected-(U34-NC-Pad38)") (class "Default")
      (node (ref "U34") (pin "38") (pinfunction "NC_38") (pintype "passive+no_connect"))
    )
    (net (code "124") (name "unconnected-(U34-NC-Pad39)") (class "Default")
      (node (ref "U34") (pin "39") (pinfunction "NC_39") (pintype "passive+no_connect"))
    )
    (net (code "125") (name "unconnected-(U34-NC-Pad42)") (class "Default")
      (node (ref "U34") (pin "42") (pinfunction "NC_42") (pintype "passive+no_connect"))
    )
    (net (code "126") (name "unconnected-(U34-NC-Pad43)") (class "Default")
      (node (ref "U34") (pin "43") (pinfunction "NC_43") (pintype "passive+no_connect"))
    )
    (net (code "127") (name "unconnected-(U34-NC-Pad66)") (class "Default")
      (node (ref "U34") (pin "66") (pinfunction "NC_66") (pintype "passive+no_connect"))
    )
    (net (code "128") (name "unconnected-(U34-NC-Pad84)") (class "Default")
      (node (ref "U34") (pin "84") (pinfunction "NC_84") (pintype "passive+no_connect"))
    )
    (net (code "129") (name "unconnected-(U34-NC{slash}DQA-Pad52)") (class "Default")
      (node (ref "U34") (pin "52") (pinfunction "NC/DQA_52") (pintype "passive+no_connect"))
    )
    (net (code "130") (name "unconnected-(U34-NC{slash}DQA-Pad53)") (class "Default")
      (node (ref "U34") (pin "53") (pinfunction "NC/DQA_53") (pintype "passive+no_connect"))
    )
    (net (code "131") (name "unconnected-(U34-NC{slash}DQA-Pad56)") (class "Default")
      (node (ref "U34") (pin "56") (pinfunction "NC/DQA_56") (pintype "passive+no_connect"))
    )
    (net (code "132") (name "unconnected-(U34-NC{slash}DQA-Pad57)") (class "Default")
      (node (ref "U34") (pin "57") (pinfunction "NC/DQA_57") (pintype "passive+no_connect"))
    )
    (net (code "133") (name "unconnected-(U34-NC{slash}DQB-Pad75)") (class "Default")
      (node (ref "U34") (pin "75") (pinfunction "NC/DQB_75") (pintype "passive+no_connect"))
    )
    (net (code "134") (name "unconnected-(U34-NC{slash}DQB-Pad78)") (class "Default")
      (node (ref "U34") (pin "78") (pinfunction "NC/DQB_78") (pintype "passive+no_connect"))
    )
    (net (code "135") (name "unconnected-(U34-NC{slash}DQB-Pad79)") (class "Default")
      (node (ref "U34") (pin "79") (pinfunction "NC/DQB_79") (pintype "passive+no_connect"))
    )
    (net (code "136") (name "unconnected-(U34-NC{slash}DQC-Pad2)") (class "Default")
      (node (ref "U34") (pin "2") (pinfunction "NC/DQC_2") (pintype "passive+no_connect"))
    )
    (net (code "137") (name "unconnected-(U34-NC{slash}DQC-Pad3)") (class "Default")
      (node (ref "U34") (pin "3") (pinfunction "NC/DQC_3") (pintype "passive"))
    )
    (net (code "138") (name "unconnected-(U34-NC{slash}DQC-Pad6)") (class "Default")
      (node (ref "U34") (pin "6") (pinfunction "NC/DQC_6") (pintype "passive+no_connect"))
    )
    (net (code "139") (name "unconnected-(U34-NC{slash}DQC-Pad7)") (class "Default")
      (node (ref "U34") (pin "7") (pinfunction "NC/DQC_7") (pintype "passive+no_connect"))
    )
    (net (code "140") (name "unconnected-(U34-NC{slash}DQD-Pad25)") (class "Default")
      (node (ref "U34") (pin "25") (pinfunction "NC/DQD_25") (pintype "passive+no_connect"))
    )
    (net (code "141") (name "unconnected-(U34-NC{slash}DQD-Pad28)") (class "Default")
      (node (ref "U34") (pin "28") (pinfunction "NC/DQD_28") (pintype "passive+no_connect"))
    )
    (net (code "142") (name "unconnected-(U34-NC{slash}DQD-Pad29)") (class "Default")
      (node (ref "U34") (pin "29") (pinfunction "NC/DQD_29") (pintype "passive+no_connect"))
    )
    (net (code "143") (name "unconnected-(U34-NC{slash}DQPA-Pad51)") (class "Default")
      (node (ref "U34") (pin "51") (pinfunction "NC/DQPA_51") (pintype "passive+no_connect"))
    )
    (net (code "144") (name "unconnected-(U34-NC{slash}DQPC-Pad1)") (class "Default")
      (node (ref "U34") (pin "1") (pinfunction "NC/DQPC_1") (pintype "passive+no_connect"))
    )
    (net (code "145") (name "unconnected-(U34-NC{slash}DQPD-Pad30)") (class "Default")
      (node (ref "U34") (pin "30") (pinfunction "NC/DQPD_30") (pintype "passive+no_connect"))
    )
    (net (code "146") (name "unconnected-(U34-NC~{{slash}BC}-Pad95)") (class "Default")
      (node (ref "U34") (pin "95") (pinfunction "NC~{/BC}_95") (pintype "passive+no_connect"))
    )
    (net (code "147") (name "unconnected-(U34-NC~{{slash}BD}-Pad96)") (class "Default")
      (node (ref "U34") (pin "96") (pinfunction "NC~{/BD}_96") (pintype "passive+no_connect"))
    )
  )
)
